# 1_V4.net
KiCad netlist of a schematic drawn in Altium Designer
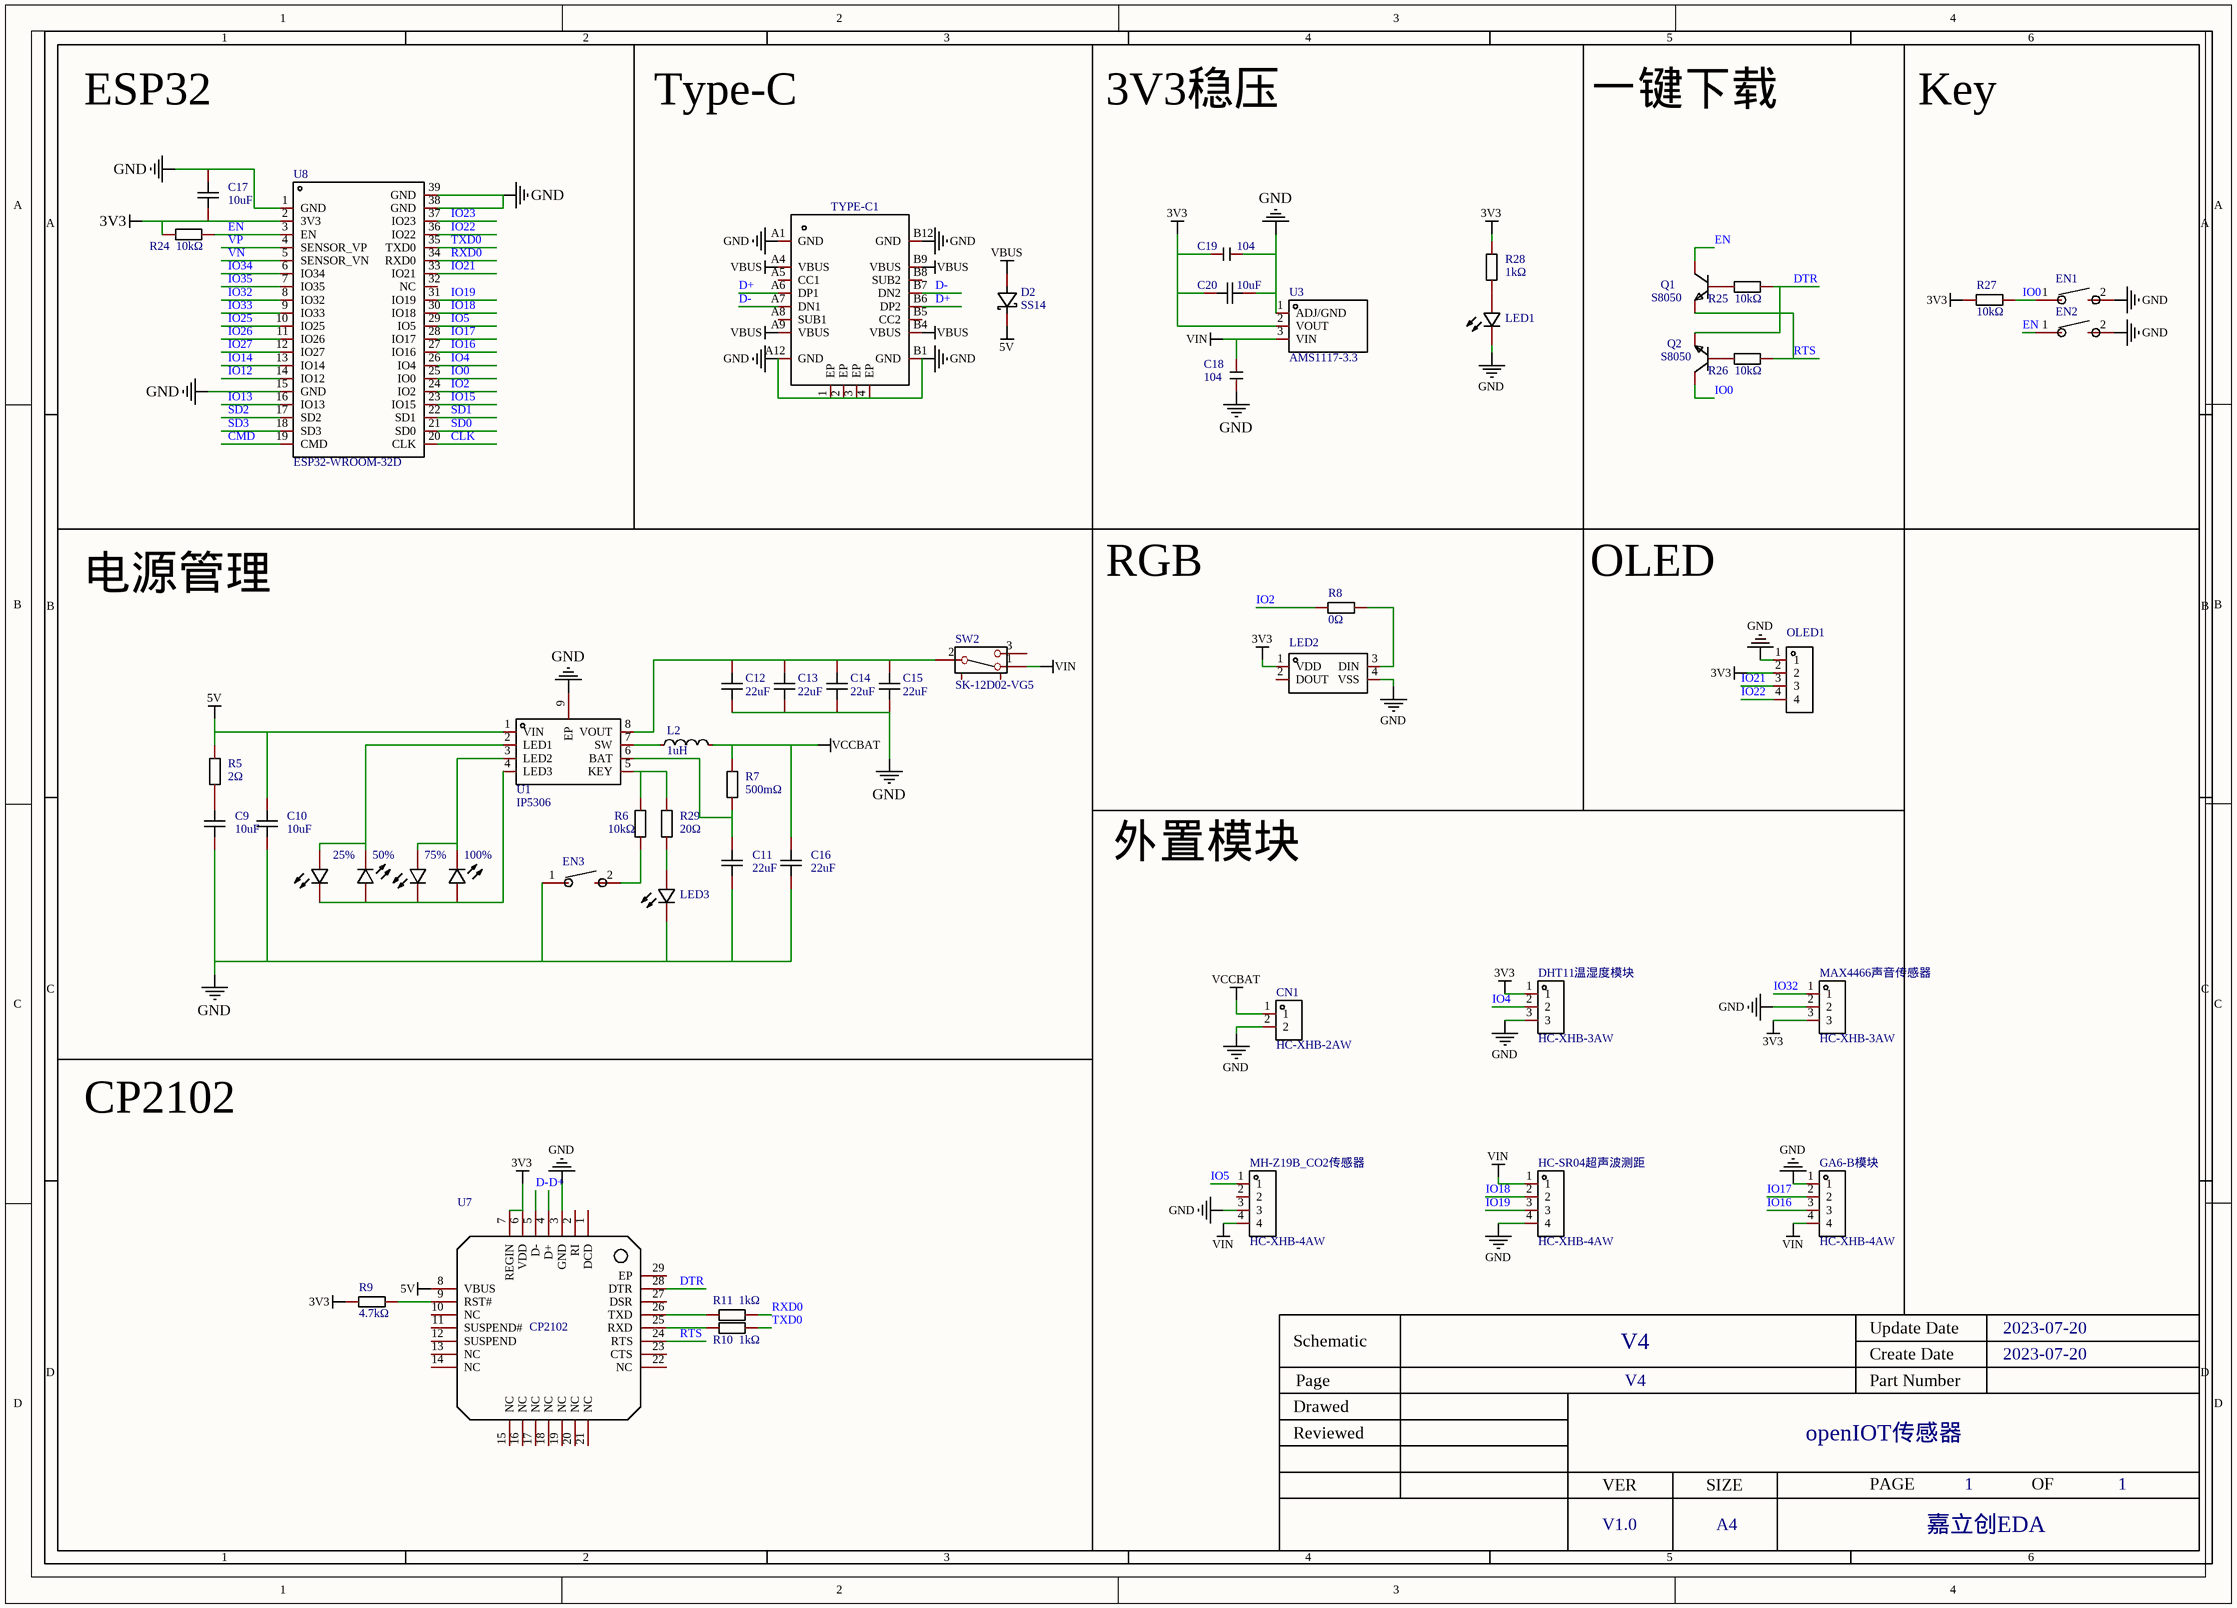
[diagram p0: 1_V4.schdoc]

(export (version "E")
  (design (tool "Eeschema 10.0.6"))
  (components
    (comp (ref "25%")
      (value "19-217/GHC-YR1S2/3T")
      (description "发光颜色:翠绿;二极管配置:-;主波长:520nm~535nm;色温:-;功率:110mW;安装方式:-;")
      (fields (field (name "MANUFACTURER") "EVERLIGHT(亿光)"))
      (libsource (lib "altium-import") (part "root_1_19-217/GHC-YR1S2/3T_"))
    )
    (comp (ref "50%")
      (value "19-217/GHC-YR1S2/3T")
      (description "发光颜色:翠绿;二极管配置:-;主波长:520nm~535nm;色温:-;功率:110mW;安装方式:-;")
      (fields (field (name "MANUFACTURER") "EVERLIGHT(亿光)"))
      (libsource (lib "altium-import") (part "root_3_19-217/GHC-YR1S2/3T_"))
    )
    (comp (ref "75%")
      (value "19-217/GHC-YR1S2/3T")
      (description "发光颜色:翠绿;二极管配置:-;主波长:520nm~535nm;色温:-;功率:110mW;安装方式:-;")
      (fields (field (name "MANUFACTURER") "EVERLIGHT(亿光)"))
      (libsource (lib "altium-import") (part "root_1_19-217/GHC-YR1S2/3T_"))
    )
    (comp (ref "100%")
      (value "19-217/GHC-YR1S2/3T")
      (description "发光颜色:翠绿;二极管配置:-;主波长:520nm~535nm;色温:-;功率:110mW;安装方式:-;")
      (fields (field (name "MANUFACTURER") "EVERLIGHT(亿光)"))
      (libsource (lib "altium-import") (part "root_3_19-217/GHC-YR1S2/3T_"))
    )
    (comp (ref "C9")
      (value "10uF")
      (description "容值:10uF;精度:±10%;额定电压:50V;材质(温度系数):X5R;")
      (fields
        (field (name "NAME") "10uF")
        (field (name "MANUFACTURER") "muRata(村田)")
        (field (name "MANUFACTURER PART") "GRM21BR61H106KE43L")
      )
      (libsource (lib "altium-import") (part "root_1_GRM21BR61H106KE43L_"))
    )
    (comp (ref "C10")
      (value "10uF")
      (description "容值:10uF;精度:±10%;额定电压:50V;材质(温度系数):X5R;")
      (fields
        (field (name "NAME") "10uF")
        (field (name "MANUFACTURER") "muRata(村田)")
        (field (name "MANUFACTURER PART") "GRM21BR61H106KE43L")
      )
      (libsource (lib "altium-import") (part "root_1_GRM21BR61H106KE43L_"))
    )
    (comp (ref "C11")
      (value "22uF")
      (description "容值:22uF;精度:±20%;额定电压:35V;材质(温度系数):X5R;")
      (fields
        (field (name "NAME") "22uF")
        (field (name "MANUFACTURER") "TDK")
        (field (name "MANUFACTURER PART") "C3216X5R1V226MTJ00E")
      )
      (libsource (lib "altium-import") (part "root_0_C3216X5R1V226MTJ00E_"))
    )
    (comp (ref "C12")
      (value "22uF")
      (description "容值:22uF;精度:±20%;额定电压:35V;材质(温度系数):X5R;")
      (fields
        (field (name "NAME") "22uF")
        (field (name "MANUFACTURER") "TDK")
        (field (name "MANUFACTURER PART") "C3216X5R1V226MTJ00E")
      )
      (libsource (lib "altium-import") (part "root_0_C3216X5R1V226MTJ00E_"))
    )
    (comp (ref "C13")
      (value "22uF")
      (description "容值:22uF;精度:±20%;额定电压:35V;材质(温度系数):X5R;")
      (fields
        (field (name "NAME") "22uF")
        (field (name "MANUFACTURER") "TDK")
        (field (name "MANUFACTURER PART") "C3216X5R1V226MTJ00E")
      )
      (libsource (lib "altium-import") (part "root_0_C3216X5R1V226MTJ00E_"))
    )
    (comp (ref "C14")
      (value "22uF")
      (description "容值:22uF;精度:±20%;额定电压:35V;材质(温度系数):X5R;")
      (fields
        (field (name "NAME") "22uF")
        (field (name "MANUFACTURER") "TDK")
        (field (name "MANUFACTURER PART") "C3216X5R1V226MTJ00E")
      )
      (libsource (lib "altium-import") (part "root_0_C3216X5R1V226MTJ00E_"))
    )
    (comp (ref "C15")
      (value "22uF")
      (description "容值:22uF;精度:±20%;额定电压:35V;材质(温度系数):X5R;")
      (fields
        (field (name "NAME") "22uF")
        (field (name "MANUFACTURER") "TDK")
        (field (name "MANUFACTURER PART") "C3216X5R1V226MTJ00E")
      )
      (libsource (lib "altium-import") (part "root_0_C3216X5R1V226MTJ00E_"))
    )
    (comp (ref "C16")
      (value "22uF")
      (description "容值:22uF;精度:±20%;额定电压:35V;材质(温度系数):X5R;")
      (fields
        (field (name "NAME") "22uF")
        (field (name "MANUFACTURER") "TDK")
        (field (name "MANUFACTURER PART") "C3216X5R1V226MTJ00E")
      )
      (libsource (lib "altium-import") (part "root_0_C3216X5R1V226MTJ00E_"))
    )
    (comp (ref "C17")
      (value "10uF")
      (description "容值:10uF;精度:±10%;额定电压:50V;材质(温度系数):X5R;")
      (fields
        (field (name "NAME") "10uF")
        (field (name "MANUFACTURER") "muRata(村田)")
        (field (name "MANUFACTURER PART") "GRM21BR61H106KE43L")
      )
      (libsource (lib "altium-import") (part "root_1_GRM21BR61H106KE43L_"))
    )
    (comp (ref "C18")
      (value "104")
      (fields (field (name "NAME") "104") (field (name "版权归属") "源创客"))
      (libsource (lib "altium-import") (part "root_1_104_"))
    )
    (comp (ref "C19")
      (value "104")
      (fields (field (name "NAME") "104") (field (name "版权归属") "源创客"))
      (libsource (lib "altium-import") (part "root_2_104_"))
    )
    (comp (ref "C20")
      (value "10uF")
      (description "容值:10uF;精度:±10%;额定电压:50V;材质(温度系数):X5R;")
      (fields
        (field (name "NAME") "10uF")
        (field (name "MANUFACTURER") "muRata(村田)")
        (field (name "MANUFACTURER PART") "GRM21BR61H106KE43L")
      )
      (libsource (lib "altium-import") (part "root_2_GRM21BR61H106KE43L_"))
    )
    (comp (ref "CN1")
      (value "HC-XHB-2AW")
      (description "参考系列:-;间距:2.5mm;插针结构:1x2P;排数:1;每排PIN数:2;行距:-;公母:公型插针;安装方式:弯插;额定电流:3A;工作温度范围:-25℃~+85℃;")
      (fields (field (name "NAME") "HC-XHB-2AW") (field (name "MANUFACTURER") "HCTL(华灿天禄)"))
      (libsource (lib "altium-import") (part "root_0_HC-XHB-2AW_C2845505_"))
    )
    (comp (ref "D2")
      (value "SS14")
      (description "二极管配置:-;直流反向耐压(Vr):40V;平均整流电流(Io):1A;正向压降(Vf):550mV@1A;反向电流(Ir):500uA@40V;")
      (fields (field (name "NAME") "SS14") (field (name "MANUFACTURER") "KUU"))
      (libsource (lib "altium-import") (part "root_1_SS14_C2909920_"))
    )
    (comp (ref "DHT11温湿度模块")
      (value "HC-XHB-3AW")
      (description "参考系列:-;间距:2.5mm;插针结构:1x3P;排数:1;每排PIN数:3;行距:-;公母:公型插针;安装方式:弯插;额定电流:3A;工作温度范围:-25℃~+85℃;")
      (fields (field (name "NAME") "HC-XHB-3AW") (field (name "MANUFACTURER") "HCTL(华灿天禄)"))
      (libsource (lib "altium-import") (part "root_0_HC-XHB-3AW_C2845506_"))
    )
    (comp (ref "EN1")
      (value "TSA343G00-250J2")
      (fields (field (name "MANUFACTURER") "BRIGHT(博瑞泰)"))
      (libsource (lib "altium-import") (part "root_0_TSA343G00-250J2_"))
    )
    (comp (ref "EN2")
      (value "TSA343G00-250J2")
      (fields (field (name "MANUFACTURER") "BRIGHT(博瑞泰)"))
      (libsource (lib "altium-import") (part "root_0_TSA343G00-250J2_"))
    )
    (comp (ref "EN3")
      (value "TSA343G00-250J2")
      (fields (field (name "MANUFACTURER") "BRIGHT(博瑞泰)"))
      (libsource (lib "altium-import") (part "root_0_TSA343G00-250J2_"))
    )
    (comp (ref "GA6-B模块")
      (value "HC-XHB-4AW")
      (description "参考系列:-;间距:2.5mm;插针结构:1x4P;排数:1;每排PIN数:4;行距:-;公母:公型插针;安装方式:弯插;额定电流:3A;工作温度范围:-25℃~+85℃;")
      (fields (field (name "NAME") "HC-XHB-4AW") (field (name "MANUFACTURER") "HCTL(华灿天禄)"))
      (libsource (lib "altium-import") (part "root_0_HC-XHB-4AW_"))
    )
    (comp (ref "HC-SR04超声波测距")
      (value "HC-XHB-4AW")
      (description "参考系列:-;间距:2.5mm;插针结构:1x4P;排数:1;每排PIN数:4;行距:-;公母:公型插针;安装方式:弯插;额定电流:3A;工作温度范围:-25℃~+85℃;")
      (fields (field (name "NAME") "HC-XHB-4AW") (field (name "MANUFACTURER") "HCTL(华灿天禄)"))
      (libsource (lib "altium-import") (part "root_0_HC-XHB-4AW_"))
    )
    (comp (ref "L2")
      (value "1uH")
      (description "电感值:1uH;精度:±20%;额定电流:8.5A;饱和电流(Isat):14A;")
      (fields
        (field (name "NAME") "1uH")
        (field (name "MANUFACTURER") "cjiang(长江微电)")
        (field (name "MANUFACTURER PART") "FXL0618-1R0-M")
      )
      (libsource (lib "altium-import") (part "root_0_FXL0618-1R0-M_"))
    )
    (comp (ref "LED1")
      (value "19-217/GHC-YR1S2/3T")
      (description "发光颜色:翠绿;二极管配置:-;主波长:520nm~535nm;色温:-;功率:110mW;安装方式:-;")
      (fields (field (name "MANUFACTURER") "EVERLIGHT(亿光)"))
      (libsource (lib "altium-import") (part "root_1_19-217/GHC-YR1S2/3T_"))
    )
    (comp (ref "LED2")
      (value "WS2812B-V5/W")
      (fields (field (name "MANUFACTURER") "worldsemi"))
      (libsource (lib "altium-import") (part "root_0_WS2812B-V5/W_"))
    )
    (comp (ref "LED3")
      (value "19-217/GHC-YR1S2/3T")
      (description "发光颜色:翠绿;二极管配置:-;主波长:520nm~535nm;色温:-;功率:110mW;安装方式:-;")
      (fields (field (name "MANUFACTURER") "EVERLIGHT(亿光)"))
      (libsource (lib "altium-import") (part "root_1_19-217/GHC-YR1S2/3T_"))
    )
    (comp (ref "MAX4466声音传感器")
      (value "HC-XHB-3AW")
      (description "参考系列:-;间距:2.5mm;插针结构:1x3P;排数:1;每排PIN数:3;行距:-;公母:公型插针;安装方式:弯插;额定电流:3A;工作温度范围:-25℃~+85℃;")
      (fields (field (name "NAME") "HC-XHB-3AW") (field (name "MANUFACTURER") "HCTL(华灿天禄)"))
      (libsource (lib "altium-import") (part "root_0_HC-XHB-3AW_C2845506_"))
    )
    (comp (ref "MH-Z19B_CO2传感器")
      (value "HC-XHB-4AW")
      (description "参考系列:-;间距:2.5mm;插针结构:1x4P;排数:1;每排PIN数:4;行距:-;公母:公型插针;安装方式:弯插;额定电流:3A;工作温度范围:-25℃~+85℃;")
      (fields (field (name "NAME") "HC-XHB-4AW") (field (name "MANUFACTURER") "HCTL(华灿天禄)"))
      (libsource (lib "altium-import") (part "root_0_HC-XHB-4AW_"))
    )
    (comp (ref "OLED1")
      (value "2.54-1*4P母")
      (fields (field (name "MANUFACTURER") "BOOMELE(博穆精密)"))
      (libsource (lib "altium-import") (part "root_0_2.54-1*4P母_"))
    )
    (comp (ref "Q1")
      (value "S8050")
      (fields (field (name "NAME") "S8050") (field (name "MANUFACTURER") "WPMtek(维攀微)"))
      (libsource (lib "altium-import") (part "root_0_S8050_"))
    )
    (comp (ref "Q2")
      (value "S8050")
      (fields (field (name "NAME") "S8050") (field (name "MANUFACTURER") "WPMtek(维攀微)"))
      (libsource (lib "altium-import") (part "root_2_S8050_"))
    )
    (comp (ref "R5")
      (value "2Ω")
      (description "电阻类型:厚膜电阻;阻值:2Ω;精度:±1%;功率:125mW;")
      (fields
        (field (name "NAME") "2Ω")
        (field (name "MANUFACTURER") "UNI-ROYAL(厚声)")
        (field (name "MANUFACTURER PART") "0805W8F200KT5E")
      )
      (libsource (lib "altium-import") (part "root_1_0805W8F200KT5E_"))
    )
    (comp (ref "R6")
      (value "10kΩ")
      (description "电阻类型:厚膜电阻;阻值:10kΩ;精度:±1%;功率:125mW;")
      (fields
        (field (name "NAME") "10kΩ")
        (field (name "MANUFACTURER") "UNI-ROYAL(厚声)")
        (field (name "MANUFACTURER PART") "0805W8F1002T5E")
      )
      (libsource (lib "altium-import") (part "root_1_0805W8F1002T5E_C17414_"))
    )
    (comp (ref "R7")
      (value "500mΩ")
      (description "电阻类型:厚膜电阻;阻值:500mΩ;精度:±1%;功率:250mW;")
      (fields
        (field (name "NAME") "500mΩ")
        (field (name "MANUFACTURER") "UNI-ROYAL(厚声)")
        (field (name "MANUFACTURER PART") "1206W4F500LT5E")
      )
      (libsource (lib "altium-import") (part "root_1_1206W4F500LT5E_"))
    )
    (comp (ref "R8")
      (value "0Ω")
      (description "电阻类型:厚膜电阻;阻值:0Ω;精度:±1%;功率:100mW;最大工作电压:75V;工作温度范围:-55℃~+155℃;")
      (fields
        (field (name "MANUFACTURER") "UNI-ROYAL(厚声)")
        (field (name "MANUFACTURER PART") "0603WAF0000T5E")
      )
      (libsource (lib "altium-import") (part "root_2_0603WAF0000T5E_"))
    )
    (comp (ref "R9")
      (value "4.7kΩ")
      (description "电阻类型:厚膜电阻;阻值:4.7kΩ;精度:±1%;功率:100mW;")
      (fields
        (field (name "NAME") "4.7kΩ")
        (field (name "MANUFACTURER") "UNI-ROYAL(厚声)")
        (field (name "MANUFACTURER PART") "0603WAF4701T5E")
      )
      (libsource (lib "altium-import") (part "root_0_0603WAF4701T5E_"))
    )
    (comp (ref "R10")
      (value "1kΩ")
      (description "电阻类型:厚膜电阻;阻值:1kΩ;精度:±1%;功率:100mW;")
      (fields
        (field (name "NAME") "1kΩ")
        (field (name "MANUFACTURER") "UNI-ROYAL(厚声)")
        (field (name "MANUFACTURER PART") "0603WAF1001T5E")
      )
      (libsource (lib "altium-import") (part "root_0_0603WAF1001T5E_"))
    )
    (comp (ref "R11")
      (value "1kΩ")
      (description "电阻类型:厚膜电阻;阻值:1kΩ;精度:±1%;功率:100mW;")
      (fields
        (field (name "NAME") "1kΩ")
        (field (name "MANUFACTURER") "UNI-ROYAL(厚声)")
        (field (name "MANUFACTURER PART") "0603WAF1001T5E")
      )
      (libsource (lib "altium-import") (part "root_0_0603WAF1001T5E_"))
    )
    (comp (ref "R24")
      (value "10kΩ")
      (description "电阻类型:厚膜电阻;阻值:10kΩ;精度:±1%;功率:100mW;")
      (fields
        (field (name "NAME") "10kΩ")
        (field (name "MANUFACTURER") "UNI-ROYAL(厚声)")
        (field (name "MANUFACTURER PART") "0603WAF1002T5E")
      )
      (libsource (lib "altium-import") (part "root_0_0603WAF1002T5E_"))
    )
    (comp (ref "R25")
      (value "10kΩ")
      (description "电阻类型:厚膜电阻;阻值:10kΩ;精度:±1%;功率:100mW;")
      (fields
        (field (name "NAME") "10kΩ")
        (field (name "MANUFACTURER") "UNI-ROYAL(厚声)")
        (field (name "MANUFACTURER PART") "0603WAF1002T5E")
      )
      (libsource (lib "altium-import") (part "root_0_0603WAF1002T5E_"))
    )
    (comp (ref "R26")
      (value "10kΩ")
      (description "电阻类型:厚膜电阻;阻值:10kΩ;精度:±1%;功率:100mW;")
      (fields
        (field (name "NAME") "10kΩ")
        (field (name "MANUFACTURER") "UNI-ROYAL(厚声)")
        (field (name "MANUFACTURER PART") "0603WAF1002T5E")
      )
      (libsource (lib "altium-import") (part "root_0_0603WAF1002T5E_"))
    )
    (comp (ref "R27")
      (value "10kΩ")
      (description "电阻类型:厚膜电阻;阻值:10kΩ;精度:±1%;功率:100mW;")
      (fields
        (field (name "NAME") "10kΩ")
        (field (name "MANUFACTURER") "UNI-ROYAL(厚声)")
        (field (name "MANUFACTURER PART") "0603WAF1002T5E")
      )
      (libsource (lib "altium-import") (part "root_2_0603WAF1002T5E_"))
    )
    (comp (ref "R28")
      (value "1kΩ")
      (description "电阻类型:厚膜电阻;阻值:1kΩ;精度:±1%;功率:100mW;")
      (fields
        (field (name "NAME") "1kΩ")
        (field (name "MANUFACTURER") "UNI-ROYAL(厚声)")
        (field (name "MANUFACTURER PART") "0603WAF1001T5E")
      )
      (libsource (lib "altium-import") (part "root_1_0603WAF1001T5E_"))
    )
    (comp (ref "R29")
      (value "20Ω")
      (description "电阻类型:厚膜电阻;阻值:20Ω;精度:±1%;功率:100mW;")
      (fields
        (field (name "NAME") "20Ω")
        (field (name "MANUFACTURER") "UNI-ROYAL(厚声)")
        (field (name "MANUFACTURER PART") "0603WAF200JT5E")
      )
      (libsource (lib "altium-import") (part "root_1_0603WAF200JT5E_"))
    )
    (comp (ref "SW2")
      (value "SK-12D02-VG5")
      (fields (field (name "NAME") "SK-12D02-VG5") (field (name "MANUFACTURER") "韩国韩荣"))
      (libsource (lib "altium-import") (part "root_0_SK-12D02-VG5_C136722_"))
    )
    (comp (ref "TYPE-C1")
      (value "KH-TYPE-C-16P")
      (description "连接器类型:Type-C;标准:-;公母:母座;触点数量:16;端口数量:1;安装方式:卧贴;额定电流 - 电源:3A;工作温度范围:-40℃~+85℃;")
      (fields (field (name "MANUFACTURER") "kinghelm(金航标)"))
      (libsource (lib "altium-import") (part "root_0_KH-TYPE-C-16P_"))
    )
    (comp (ref "U1")
      (value "IP5306")
      (description "2.1A充电2.4A放电高集成度移动电源SOC")
      (fields (field (name "NAME") "IP5306") (field (name "MANUFACTURER") "INJOINIC(英集芯)"))
      (libsource (lib "altium-import") (part "root_0_IP5306_"))
    )
    (comp (ref "U3")
      (value "AMS1117-3.3")
      (description "输出类型:-;")
      (fields (field (name "NAME") "AMS1117-3.3") (field (name "MANUFACTURER") "Slkor(萨科微)"))
      (libsource (lib "altium-import") (part "root_0_AMS1117-3.3_C880752_"))
    )
    (comp (ref "U7")
      (value "CP2102")
      (description "类型:Transceiver;协议类别:USB;驱动器/接收器数:1/1;数据速率:1Mbps;")
      (fields (field (name "NAME") "CP2102") (field (name "MANUFACTURER") "SILICON LABS(芯科)"))
      (libsource (lib "altium-import") (part "root_3_CP2102-GMR_"))
    )
    (comp (ref "U8")
      (value "ESP32-WROOM-32D")
      (fields (field (name "NAME") "ESP32-WROOM-32D"))
      (libsource (lib "altium-import") (part "root_0_ESP32-WROOM-32D_"))
    )
  )
  (nets
    (net (code "1") (name "/CLK") (class "Default")
      (node (ref "U8") (pin "20") (pinfunction "CLK_20") (pintype "passive"))
    )
    (net (code "2") (name "/CMD") (class "Default")
      (node (ref "U8") (pin "19") (pinfunction "CMD_19") (pintype "passive"))
    )
    (net (code "3") (name "/D+") (class "Default")
      (node (ref "TYPE-C1") (pin "A6") (pinfunction "DP1_A6") (pintype "passive"))
      (node (ref "TYPE-C1") (pin "B6") (pinfunction "DP2_B6") (pintype "passive"))
      (node (ref "U7") (pin "4") (pinfunction "D+_4") (pintype "passive"))
    )
    (net (code "4") (name "/D-") (class "Default")
      (node (ref "TYPE-C1") (pin "A7") (pinfunction "DN1_A7") (pintype "passive"))
      (node (ref "TYPE-C1") (pin "B7") (pinfunction "DN2_B7") (pintype "passive"))
      (node (ref "U7") (pin "5") (pinfunction "D-_5") (pintype "passive"))
    )
    (net (code "5") (name "/DTR") (class "Default")
      (node (ref "Q2") (pin "2") (pinfunction "E_2") (pintype "passive"))
      (node (ref "R25") (pin "2") (pinfunction "2_2") (pintype "passive"))
      (node (ref "U7") (pin "28") (pinfunction "DTR_28") (pintype "passive"))
    )
    (net (code "6") (name "/EN") (class "Default")
      (node (ref "EN2") (pin "1") (pinfunction "1_1") (pintype "passive"))
      (node (ref "Q1") (pin "3") (pinfunction "C_3") (pintype "passive"))
      (node (ref "R24") (pin "2") (pinfunction "2_2") (pintype "passive"))
      (node (ref "U8") (pin "3") (pinfunction "EN_3") (pintype "passive"))
    )
    (net (code "7") (name "/IO0") (class "Default")
      (node (ref "EN1") (pin "1") (pinfunction "1_1") (pintype "passive"))
      (node (ref "Q2") (pin "3") (pinfunction "C_3") (pintype "passive"))
      (node (ref "R27") (pin "1") (pinfunction "1_1") (pintype "passive"))
      (node (ref "U8") (pin "25") (pinfunction "IO0_25") (pintype "passive"))
    )
    (net (code "8") (name "/IO2") (class "Default")
      (node (ref "R8") (pin "2") (pinfunction "2_2") (pintype "passive"))
      (node (ref "U8") (pin "24") (pinfunction "IO2_24") (pintype "passive"))
    )
    (net (code "9") (name "/IO4") (class "Default")
      (node (ref "DHT11温湿度模块") (pin "2") (pinfunction "2_2") (pintype "passive"))
      (node (ref "U8") (pin "26") (pinfunction "IO4_26") (pintype "passive"))
    )
    (net (code "10") (name "/IO5") (class "Default")
      (node (ref "MH-Z19B_CO2传感器") (pin "1") (pinfunction "1_1") (pintype "passive"))
      (node (ref "U8") (pin "29") (pinfunction "IO5_29") (pintype "passive"))
    )
    (net (code "11") (name "/IO12") (class "Default")
      (node (ref "U8") (pin "14") (pinfunction "IO12_14") (pintype "passive"))
    )
    (net (code "12") (name "/IO13") (class "Default")
      (node (ref "U8") (pin "16") (pinfunction "IO13_16") (pintype "passive"))
    )
    (net (code "13") (name "/IO14") (class "Default")
      (node (ref "U8") (pin "13") (pinfunction "IO14_13") (pintype "passive"))
    )
    (net (code "14") (name "/IO15") (class "Default")
      (node (ref "U8") (pin "23") (pinfunction "IO15_23") (pintype "passive"))
    )
    (net (code "15") (name "/IO16") (class "Default")
      (node (ref "GA6-B模块") (pin "3") (pinfunction "3_3") (pintype "passive"))
      (node (ref "U8") (pin "27") (pinfunction "IO16_27") (pintype "passive"))
    )
    (net (code "16") (name "/IO17") (class "Default")
      (node (ref "GA6-B模块") (pin "2") (pinfunction "2_2") (pintype "passive"))
      (node (ref "U8") (pin "28") (pinfunction "IO17_28") (pintype "passive"))
    )
    (net (code "17") (name "/IO18") (class "Default")
      (node (ref "HC-SR04超声波测距") (pin "2") (pinfunction "2_2") (pintype "passive"))
      (node (ref "U8") (pin "30") (pinfunction "IO18_30") (pintype "passive"))
    )
    (net (code "18") (name "/IO19") (class "Default")
      (node (ref "HC-SR04超声波测距") (pin "3") (pinfunction "3_3") (pintype "passive"))
      (node (ref "U8") (pin "31") (pinfunction "IO19_31") (pintype "passive"))
    )
    (net (code "19") (name "/IO21") (class "Default")
      (node (ref "OLED1") (pin "3") (pinfunction "3_3") (pintype "passive"))
      (node (ref "U8") (pin "33") (pinfunction "IO21_33") (pintype "passive"))
    )
    (net (code "20") (name "/IO22") (class "Default")
      (node (ref "OLED1") (pin "4") (pinfunction "4_4") (pintype "passive"))
      (node (ref "U8") (pin "36") (pinfunction "IO22_36") (pintype "passive"))
    )
    (net (code "21") (name "/IO23") (class "Default")
      (node (ref "U8") (pin "37") (pinfunction "IO23_37") (pintype "passive"))
    )
    (net (code "22") (name "/IO25") (class "Default")
      (node (ref "U8") (pin "10") (pinfunction "IO25_10") (pintype "passive"))
    )
    (net (code "23") (name "/IO26") (class "Default")
      (node (ref "U8") (pin "11") (pinfunction "IO26_11") (pintype "passive"))
    )
    (net (code "24") (name "/IO27") (class "Default")
      (node (ref "U8") (pin "12") (pinfunction "IO27_12") (pintype "passive"))
    )
    (net (code "25") (name "/IO32") (class "Default")
      (node (ref "MAX4466声音传感器") (pin "1") (pinfunction "1_1") (pintype "passive"))
      (node (ref "U8") (pin "8") (pinfunction "IO32_8") (pintype "passive"))
    )
    (net (code "26") (name "/IO33") (class "Default")
      (node (ref "U8") (pin "9") (pinfunction "IO33_9") (pintype "passive"))
    )
    (net (code "27") (name "/IO34") (class "Default")
      (node (ref "U8") (pin "6") (pinfunction "IO34_6") (pintype "passive"))
    )
    (net (code "28") (name "/IO35") (class "Default")
      (node (ref "U8") (pin "7") (pinfunction "IO35_7") (pintype "passive"))
    )
    (net (code "29") (name "/RTS") (class "Default")
      (node (ref "Q1") (pin "2") (pinfunction "E_2") (pintype "passive"))
      (node (ref "R26") (pin "2") (pinfunction "2_2") (pintype "passive"))
      (node (ref "U7") (pin "24") (pinfunction "RTS_24") (pintype "passive"))
    )
    (net (code "30") (name "/RXD0") (class "Default")
      (node (ref "R11") (pin "2") (pinfunction "2_2") (pintype "passive"))
      (node (ref "U8") (pin "34") (pinfunction "RXD0_34") (pintype "passive"))
    )
    (net (code "31") (name "/SD0") (class "Default")
      (node (ref "U8") (pin "21") (pinfunction "SD0_21") (pintype "passive"))
    )
    (net (code "32") (name "/SD1") (class "Default")
      (node (ref "U8") (pin "22") (pinfunction "SD1_22") (pintype "passive"))
    )
    (net (code "33") (name "/SD2") (class "Default")
      (node (ref "U8") (pin "17") (pinfunction "SD2_17") (pintype "passive"))
    )
    (net (code "34") (name "/SD3") (class "Default")
      (node (ref "U8") (pin "18") (pinfunction "SD3_18") (pintype "passive"))
    )
    (net (code "35") (name "/TXD0") (class "Default")
      (node (ref "R10") (pin "2") (pinfunction "2_2") (pintype "passive"))
      (node (ref "U8") (pin "35") (pinfunction "TXD0_35") (pintype "passive"))
    )
    (net (code "36") (name "/VN") (class "Default")
      (node (ref "U8") (pin "5") (pinfunction "SENSOR_VN_5") (pintype "passive"))
    )
    (net (code "37") (name "/VP") (class "Default")
      (node (ref "U8") (pin "4") (pinfunction "SENSOR_VP_4") (pintype "passive"))
    )
    (net (code "38") (name "3V3") (class "Default")
      (node (ref "C17") (pin "1") (pinfunction "1_1") (pintype "passive"))
      (node (ref "C19") (pin "2") (pinfunction "2_2") (pintype "passive"))
      (node (ref "C20") (pin "2") (pinfunction "2_2") (pintype "passive"))
      (node (ref "DHT11温湿度模块") (pin "1") (pinfunction "1_1") (pintype "passive"))
      (node (ref "LED2") (pin "1") (pinfunction "VDD_1") (pintype "passive"))
      (node (ref "MAX4466声音传感器") (pin "3") (pinfunction "3_3") (pintype "passive"))
      (node (ref "OLED1") (pin "2") (pinfunction "2_2") (pintype "passive"))
      (node (ref "R24") (pin "1") (pinfunction "1_1") (pintype "passive"))
      (node (ref "R27") (pin "2") (pinfunction "2_2") (pintype "passive"))
      (node (ref "R28") (pin "2") (pinfunction "2_2") (pintype "passive"))
      (node (ref "R9") (pin "1") (pinfunction "1_1") (pintype "passive"))
      (node (ref "U3") (pin "2") (pinfunction "VOUT_2") (pintype "passive"))
      (node (ref "U7") (pin "6") (pinfunction "VDD_6") (pintype "passive"))
      (node (ref "U7") (pin "7") (pinfunction "REGIN_7") (pintype "passive"))
      (node (ref "U8") (pin "2") (pinfunction "3V3_2") (pintype "passive"))
    )
    (net (code "39") (name "5V") (class "Default")
      (node (ref "C10") (pin "2") (pinfunction "2_2") (pintype "passive"))
      (node (ref "D2") (pin "1") (pinfunction "A_1") (pintype "passive"))
      (node (ref "R5") (pin "2") (pinfunction "2_2") (pintype "passive"))
      (node (ref "U1") (pin "1") (pinfunction "VIN_1") (pintype "passive"))
      (node (ref "U7") (pin "8") (pinfunction "VBUS_8") (pintype "passive"))
    )
    (net (code "40") (name "GND") (class "Default")
      (node (ref "C10") (pin "1") (pinfunction "1_1") (pintype "passive"))
      (node (ref "C11") (pin "1") (pinfunction "1_1") (pintype "passive"))
      (node (ref "C12") (pin "1") (pinfunction "1_1") (pintype "passive"))
      (node (ref "C13") (pin "1") (pinfunction "1_1") (pintype "passive"))
      (node (ref "C14") (pin "1") (pinfunction "1_1") (pintype "passive"))
      (node (ref "C15") (pin "1") (pinfunction "1_1") (pintype "passive"))
      (node (ref "C16") (pin "1") (pinfunction "1_1") (pintype "passive"))
      (node (ref "C17") (pin "2") (pinfunction "2_2") (pintype "passive"))
      (node (ref "C18") (pin "1") (pinfunction "1_1") (pintype "passive"))
      (node (ref "C19") (pin "1") (pinfunction "1_1") (pintype "passive"))
      (node (ref "C20") (pin "1") (pinfunction "1_1") (pintype "passive"))
      (node (ref "C9") (pin "1") (pinfunction "1_1") (pintype "passive"))
      (node (ref "CN1") (pin "2") (pinfunction "2_2") (pintype "passive"))
      (node (ref "DHT11温湿度模块") (pin "3") (pinfunction "3_3") (pintype "passive"))
      (node (ref "EN1") (pin "2") (pinfunction "2_2") (pintype "passive"))
      (node (ref "EN2") (pin "2") (pinfunction "2_2") (pintype "passive"))
      (node (ref "EN3") (pin "1") (pinfunction "1_1") (pintype "passive"))
      (node (ref "GA6-B模块") (pin "1") (pinfunction "1_1") (pintype "passive"))
      (node (ref "HC-SR04超声波测距") (pin "4") (pinfunction "4_4") (pintype "passive"))
      (node (ref "LED1") (pin "1") (pinfunction "C_1") (pintype "passive"))
      (node (ref "LED2") (pin "4") (pinfunction "VSS_4") (pintype "passive"))
      (node (ref "LED3") (pin "1") (pinfunction "C_1") (pintype "passive"))
      (node (ref "MAX4466声音传感器") (pin "2") (pinfunction "2_2") (pintype "passive"))
      (node (ref "MH-Z19B_CO2传感器") (pin "3") (pinfunction "3_3") (pintype "passive"))
      (node (ref "OLED1") (pin "1") (pinfunction "1_1") (pintype "passive"))
      (node (ref "TYPE-C1") (pin "1") (pinfunction "EP_1") (pintype "passive"))
      (node (ref "TYPE-C1") (pin "2") (pinfunction "EP_2") (pintype "passive"))
      (node (ref "TYPE-C1") (pin "3") (pinfunction "EP_3") (pintype "passive"))
      (node (ref "TYPE-C1") (pin "4") (pinfunction "EP_4") (pintype "passive"))
      (node (ref "TYPE-C1") (pin "A1") (pinfunction "GND_A1") (pintype "passive"))
      (node (ref "TYPE-C1") (pin "A12") (pinfunction "GND_A12") (pintype "passive"))
      (node (ref "TYPE-C1") (pin "B1") (pinfunction "GND_B1") (pintype "passive"))
      (node (ref "TYPE-C1") (pin "B12") (pinfunction "GND_B12") (pintype "passive"))
      (node (ref "U1") (pin "9") (pinfunction "EP_9") (pintype "passive"))
      (node (ref "U3") (pin "1") (pinfunction "ADJ/GND_1") (pintype "passive"))
      (node (ref "U7") (pin "3") (pinfunction "GND_3") (pintype "passive"))
      (node (ref "U8") (pin "1") (pinfunction "GND_1") (pintype "passive"))
      (node (ref "U8") (pin "15") (pinfunction "GND_15") (pintype "passive"))
      (node (ref "U8") (pin "38") (pinfunction "GND_38") (pintype "passive"))
      (node (ref "U8") (pin "39") (pinfunction "GND_39") (pintype "passive"))
    )
    (net (code "41") (name "Net-(25%-A)") (class "Default")
      (node (ref "25%") (pin "2") (pinfunction "A_2") (pintype "passive"))
      (node (ref "50%") (pin "1") (pinfunction "C_1") (pintype "passive"))
      (node (ref "U1") (pin "2") (pinfunction "LED1_2") (pintype "passive"))
    )
    (net (code "42") (name "Net-(100%-A)") (class "Default")
      (node (ref "100%") (pin "2") (pinfunction "A_2") (pintype "passive"))
      (node (ref "25%") (pin "1") (pinfunction "C_1") (pintype "passive"))
      (node (ref "50%") (pin "2") (pinfunction "A_2") (pintype "passive"))
      (node (ref "75%") (pin "1") (pinfunction "C_1") (pintype "passive"))
      (node (ref "U1") (pin "4") (pinfunction "LED3_4") (pintype "passive"))
    )
    (net (code "43") (name "Net-(100%-C)") (class "Default")
      (node (ref "100%") (pin "1") (pinfunction "C_1") (pintype "passive"))
      (node (ref "75%") (pin "2") (pinfunction "A_2") (pintype "passive"))
      (node (ref "U1") (pin "3") (pinfunction "LED2_3") (pintype "passive"))
    )
    (net (code "44") (name "Net-(C9-Pad2)") (class "Default")
      (node (ref "C9") (pin "2") (pinfunction "2_2") (pintype "passive"))
      (node (ref "R5") (pin "1") (pinfunction "1_1") (pintype "passive"))
    )
    (net (code "45") (name "Net-(EN3-Pad2)") (class "Default")
      (node (ref "EN3") (pin "2") (pinfunction "2_2") (pintype "passive"))
      (node (ref "R6") (pin "1") (pinfunction "1_1") (pintype "passive"))
    )
    (net (code "46") (name "Net-(LED1-A)") (class "Default")
      (node (ref "LED1") (pin "2") (pinfunction "A_2") (pintype "passive"))
      (node (ref "R28") (pin "1") (pinfunction "1_1") (pintype "passive"))
    )
    (net (code "47") (name "Net-(LED2-DIN)") (class "Default")
      (node (ref "LED2") (pin "3") (pinfunction "DIN_3") (pintype "passive"))
      (node (ref "R8") (pin "1") (pinfunction "1_1") (pintype "passive"))
    )
    (net (code "48") (name "Net-(LED3-A)") (class "Default")
      (node (ref "LED3") (pin "2") (pinfunction "A_2") (pintype "passive"))
      (node (ref "R29") (pin "1") (pinfunction "1_1") (pintype "passive"))
    )
    (net (code "49") (name "Net-(Q1-B)") (class "Default")
      (node (ref "Q1") (pin "1") (pinfunction "B_1") (pintype "passive"))
      (node (ref "R25") (pin "1") (pinfunction "1_1") (pintype "passive"))
    )
    (net (code "50") (name "Net-(Q2-B)") (class "Default")
      (node (ref "Q2") (pin "1") (pinfunction "B_1") (pintype "passive"))
      (node (ref "R26") (pin "1") (pinfunction "1_1") (pintype "passive"))
    )
    (net (code "51") (name "Net-(U1-BAT)") (class "Default")
      (node (ref "C11") (pin "2") (pinfunction "2_2") (pintype "passive"))
      (node (ref "R7") (pin "1") (pinfunction "1_1") (pintype "passive"))
      (node (ref "U1") (pin "6") (pinfunction "BAT_6") (pintype "passive"))
    )
    (net (code "52") (name "Net-(U1-KEY)") (class "Default")
      (node (ref "R29") (pin "2") (pinfunction "2_2") (pintype "passive"))
      (node (ref "R6") (pin "2") (pinfunction "2_2") (pintype "passive"))
      (node (ref "U1") (pin "5") (pinfunction "KEY_5") (pintype "passive"))
    )
    (net (code "53") (name "Net-(U1-SW)") (class "Default")
      (node (ref "L2") (pin "1") (pinfunction "1_1") (pintype "passive"))
      (node (ref "U1") (pin "7") (pinfunction "SW_7") (pintype "passive"))
    )
    (net (code "54") (name "Net-(U1-VOUT)") (class "Default")
      (node (ref "C12") (pin "2") (pinfunction "2_2") (pintype "passive"))
      (node (ref "C13") (pin "2") (pinfunction "2_2") (pintype "passive"))
      (node (ref "C14") (pin "2") (pinfunction "2_2") (pintype "passive"))
      (node (ref "C15") (pin "2") (pinfunction "2_2") (pintype "passive"))
      (node (ref "SW2") (pin "2") (pinfunction "2_2") (pintype "passive"))
      (node (ref "U1") (pin "8") (pinfunction "VOUT_8") (pintype "passive"))
    )
    (net (code "55") (name "Net-(U7-RST#)") (class "Default")
      (node (ref "R9") (pin "2") (pinfunction "2_2") (pintype "passive"))
      (node (ref "U7") (pin "9") (pinfunction "RST#_9") (pintype "passive"))
    )
    (net (code "56") (name "Net-(U7-RXD)") (class "Default")
      (node (ref "R10") (pin "1") (pinfunction "1_1") (pintype "passive"))
      (node (ref "U7") (pin "25") (pinfunction "RXD_25") (pintype "passive"))
    )
    (net (code "57") (name "Net-(U7-TXD)") (class "Default")
      (node (ref "R11") (pin "1") (pinfunction "1_1") (pintype "passive"))
      (node (ref "U7") (pin "26") (pinfunction "TXD_26") (pintype "passive"))
    )
    (net (code "58") (name "VBUS") (class "Default")
      (node (ref "D2") (pin "2") (pinfunction "K_2") (pintype "passive"))
      (node (ref "TYPE-C1") (pin "A4") (pinfunction "VBUS_A4") (pintype "passive"))
      (node (ref "TYPE-C1") (pin "A9") (pinfunction "VBUS_A9") (pintype "passive"))
      (node (ref "TYPE-C1") (pin "B4") (pinfunction "VBUS_B4") (pintype "passive"))
      (node (ref "TYPE-C1") (pin "B9") (pinfunction "VBUS_B9") (pintype "passive"))
    )
    (net (code "59") (name "VCCBAT") (class "Default")
      (node (ref "C16") (pin "2") (pinfunction "2_2") (pintype "passive"))
      (node (ref "CN1") (pin "1") (pinfunction "1_1") (pintype "passive"))
      (node (ref "L2") (pin "2") (pinfunction "2_2") (pintype "passive"))
      (node (ref "R7") (pin "2") (pinfunction "2_2") (pintype "passive"))
    )
    (net (code "60") (name "VIN") (class "Default")
      (node (ref "C18") (pin "2") (pinfunction "2_2") (pintype "passive"))
      (node (ref "GA6-B模块") (pin "4") (pinfunction "4_4") (pintype "passive"))
      (node (ref "HC-SR04超声波测距") (pin "1") (pinfunction "1_1") (pintype "passive"))
      (node (ref "MH-Z19B_CO2传感器") (pin "4") (pinfunction "4_4") (pintype "passive"))
      (node (ref "SW2") (pin "1") (pinfunction "1_1") (pintype "passive"))
      (node (ref "U3") (pin "3") (pinfunction "VIN_3") (pintype "passive"))
    )
    (net (code "61") (name "unconnected-(LED2-DOUT-Pad2)") (class "Default")
      (node (ref "LED2") (pin "2") (pinfunction "DOUT_2") (pintype "passive"))
    )
    (net (code "62") (name "unconnected-(MH-Z19B_CO2传感器-Pad2)") (class "Default")
      (node (ref "MH-Z19B_CO2传感器") (pin "2") (pinfunction "2_2") (pintype "passive"))
    )
    (net (code "63") (name "unconnected-(SW2-Pad3)") (class "Default")
      (node (ref "SW2") (pin "3") (pinfunction "3_3") (pintype "passive"))
    )
    (net (code "64") (name "unconnected-(SW2-Pad4)") (class "Default")
      (node (ref "SW2") (pin "4") (pinfunction "4_4") (pintype "passive"))
    )
    (net (code "65") (name "unconnected-(SW2-Pad5)") (class "Default")
      (node (ref "SW2") (pin "5") (pinfunction "5_5") (pintype "passive"))
    )
    (net (code "66") (name "unconnected-(TYPE-C1-CC1-PadA5)") (class "Default")
      (node (ref "TYPE-C1") (pin "A5") (pinfunction "CC1_A5") (pintype "passive"))
    )
    (net (code "67") (name "unconnected-(TYPE-C1-CC2-PadB5)") (class "Default")
      (node (ref "TYPE-C1") (pin "B5") (pinfunction "CC2_B5") (pintype "passive"))
    )
    (net (code "68") (name "unconnected-(TYPE-C1-SUB1-PadA8)") (class "Default")
      (node (ref "TYPE-C1") (pin "A8") (pinfunction "SUB1_A8") (pintype "passive"))
    )
    (net (code "69") (name "unconnected-(TYPE-C1-SUB2-PadB8)") (class "Default")
      (node (ref "TYPE-C1") (pin "B8") (pinfunction "SUB2_B8") (pintype "passive"))
    )
    (net (code "70") (name "unconnected-(U7-CTS-Pad23)") (class "Default")
      (node (ref "U7") (pin "23") (pinfunction "CTS_23") (pintype "passive"))
    )
    (net (code "71") (name "unconnected-(U7-DCD-Pad1)") (class "Default")
      (node (ref "U7") (pin "1") (pinfunction "DCD_1") (pintype "passive"))
    )
    (net (code "72") (name "unconnected-(U7-DSR-Pad27)") (class "Default")
      (node (ref "U7") (pin "27") (pinfunction "DSR_27") (pintype "passive"))
    )
    (net (code "73") (name "unconnected-(U7-EP-Pad29)") (class "Default")
      (node (ref "U7") (pin "29") (pinfunction "EP_29") (pintype "passive"))
    )
    (net (code "74") (name "unconnected-(U7-NC-Pad10)") (class "Default")
      (node (ref "U7") (pin "10") (pinfunction "NC_10") (pintype "passive"))
    )
    (net (code "75") (name "unconnected-(U7-NC-Pad13)") (class "Default")
      (node (ref "U7") (pin "13") (pinfunction "NC_13") (pintype "passive"))
    )
    (net (code "76") (name "unconnected-(U7-NC-Pad14)") (class "Default")
      (node (ref "U7") (pin "14") (pinfunction "NC_14") (pintype "passive"))
    )
    (net (code "77") (name "unconnected-(U7-NC-Pad15)") (class "Default")
      (node (ref "U7") (pin "15") (pinfunction "NC_15") (pintype "passive"))
    )
    (net (code "78") (name "unconnected-(U7-NC-Pad16)") (class "Default")
      (node (ref "U7") (pin "16") (pinfunction "NC_16") (pintype "passive"))
    )
    (net (code "79") (name "unconnected-(U7-NC-Pad17)") (class "Default")
      (node (ref "U7") (pin "17") (pinfunction "NC_17") (pintype "passive"))
    )
    (net (code "80") (name "unconnected-(U7-NC-Pad18)") (class "Default")
      (node (ref "U7") (pin "18") (pinfunction "NC_18") (pintype "passive"))
    )
    (net (code "81") (name "unconnected-(U7-NC-Pad19)") (class "Default")
      (node (ref "U7") (pin "19") (pinfunction "NC_19") (pintype "passive"))
    )
    (net (code "82") (name "unconnected-(U7-NC-Pad20)") (class "Default")
      (node (ref "U7") (pin "20") (pinfunction "NC_20") (pintype "passive"))
    )
    (net (code "83") (name "unconnected-(U7-NC-Pad21)") (class "Default")
      (node (ref "U7") (pin "21") (pinfunction "NC_21") (pintype "passive"))
    )
    (net (code "84") (name "unconnected-(U7-NC-Pad22)") (class "Default")
      (node (ref "U7") (pin "22") (pinfunction "NC_22") (pintype "passive"))
    )
    (net (code "85") (name "unconnected-(U7-RI-Pad2)") (class "Default")
      (node (ref "U7") (pin "2") (pinfunction "RI_2") (pintype "passive"))
    )
    (net (code "86") (name "unconnected-(U7-SUSPEND#-Pad11)") (class "Default")
      (node (ref "U7") (pin "11") (pinfunction "SUSPEND#_11") (pintype "passive"))
    )
    (net (code "87") (name "unconnected-(U7-SUSPEND-Pad12)") (class "Default")
      (node (ref "U7") (pin "12") (pinfunction "SUSPEND_12") (pintype "passive"))
    )
    (net (code "88") (name "unconnected-(U8-NC-Pad32)") (class "Default")
      (node (ref "U8") (pin "32") (pinfunction "NC_32") (pintype "passive"))
    )
  )
)
